# FET_mux_2layer.net
KiCad netlist of a schematic drawn in EAGLE
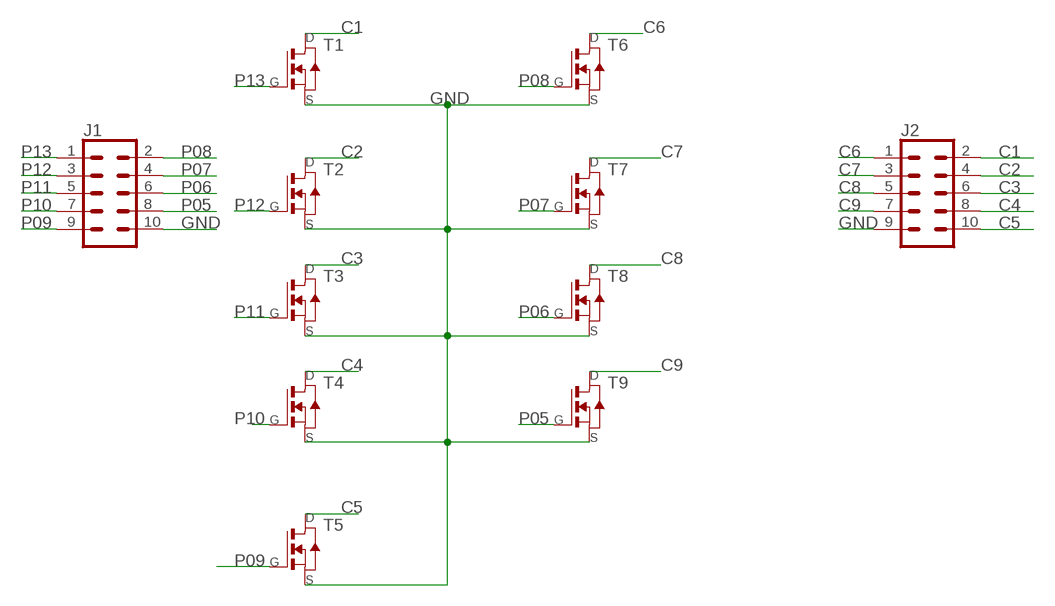
[diagram p0: schematic, sheet 1]

(export (version "E")
  (design (tool "Eeschema 10.0.6"))
  (components
    (comp (ref "J1")
      (value "CONN_05X2SHD_SMD")
      (footprint "eagle-import:2X5-SHROUDED_SMD")
      (libsource (lib "eagle-import") (part "CONN_05X2SHD_SMD"))
    )
    (comp (ref "J2")
      (value "CONN_05X2SHD_SMD")
      (footprint "eagle-import:2X5-SHROUDED_SMD")
      (libsource (lib "eagle-import") (part "CONN_05X2SHD_SMD"))
    )
    (comp (ref "T1")
      (value "NMOSFETSOT23")
      (footprint "eagle-import:SOT-23")
      (libsource (lib "eagle-import") (part "NMOSFETSOT23"))
    )
    (comp (ref "T2")
      (value "NMOSFETSOT23")
      (footprint "eagle-import:SOT-23")
      (libsource (lib "eagle-import") (part "NMOSFETSOT23"))
    )
    (comp (ref "T3")
      (value "NMOSFETSOT23")
      (footprint "eagle-import:SOT-23")
      (libsource (lib "eagle-import") (part "NMOSFETSOT23"))
    )
    (comp (ref "T4")
      (value "NMOSFETSOT23")
      (footprint "eagle-import:SOT-23")
      (libsource (lib "eagle-import") (part "NMOSFETSOT23"))
    )
    (comp (ref "T5")
      (value "NMOSFETSOT23")
      (footprint "eagle-import:SOT-23")
      (libsource (lib "eagle-import") (part "NMOSFETSOT23"))
    )
    (comp (ref "T6")
      (value "NMOSFETSOT23")
      (footprint "eagle-import:SOT-23")
      (libsource (lib "eagle-import") (part "NMOSFETSOT23"))
    )
    (comp (ref "T7")
      (value "NMOSFETSOT23")
      (footprint "eagle-import:SOT-23")
      (libsource (lib "eagle-import") (part "NMOSFETSOT23"))
    )
    (comp (ref "T8")
      (value "NMOSFETSOT23")
      (footprint "eagle-import:SOT-23")
      (libsource (lib "eagle-import") (part "NMOSFETSOT23"))
    )
    (comp (ref "T9")
      (value "NMOSFETSOT23")
      (footprint "eagle-import:SOT-23")
      (libsource (lib "eagle-import") (part "NMOSFETSOT23"))
    )
  )
  (nets
    (net (code "1") (name "/C1") (class "Default")
      (node (ref "J2") (pin "2") (pinfunction "2_2") (pintype "passive"))
      (node (ref "T1") (pin "1") (pinfunction "D_1") (pintype "passive"))
    )
    (net (code "2") (name "/C2") (class "Default")
      (node (ref "J2") (pin "4") (pinfunction "4_4") (pintype "passive"))
      (node (ref "T2") (pin "1") (pinfunction "D_1") (pintype "passive"))
    )
    (net (code "3") (name "/C3") (class "Default")
      (node (ref "J2") (pin "6") (pinfunction "6_6") (pintype "passive"))
      (node (ref "T3") (pin "1") (pinfunction "D_1") (pintype "passive"))
    )
    (net (code "4") (name "/C4") (class "Default")
      (node (ref "J2") (pin "8") (pinfunction "8_8") (pintype "passive"))
      (node (ref "T4") (pin "1") (pinfunction "D_1") (pintype "passive"))
    )
    (net (code "5") (name "/C5") (class "Default")
      (node (ref "J2") (pin "10") (pinfunction "10_10") (pintype "passive"))
      (node (ref "T5") (pin "1") (pinfunction "D_1") (pintype "passive"))
    )
    (net (code "6") (name "/C6") (class "Default")
      (node (ref "J2") (pin "1") (pinfunction "1_1") (pintype "passive"))
      (node (ref "T6") (pin "1") (pinfunction "D_1") (pintype "passive"))
    )
    (net (code "7") (name "/C7") (class "Default")
      (node (ref "J2") (pin "3") (pinfunction "3_3") (pintype "passive"))
      (node (ref "T7") (pin "1") (pinfunction "D_1") (pintype "passive"))
    )
    (net (code "8") (name "/C8") (class "Default")
      (node (ref "J2") (pin "5") (pinfunction "5_5") (pintype "passive"))
      (node (ref "T8") (pin "1") (pinfunction "D_1") (pintype "passive"))
    )
    (net (code "9") (name "/C9") (class "Default")
      (node (ref "J2") (pin "7") (pinfunction "7_7") (pintype "passive"))
      (node (ref "T9") (pin "1") (pinfunction "D_1") (pintype "passive"))
    )
    (net (code "10") (name "/GND") (class "Default")
      (node (ref "J1") (pin "10") (pinfunction "10_10") (pintype "passive"))
      (node (ref "J2") (pin "9") (pinfunction "9_9") (pintype "passive"))
      (node (ref "T1") (pin "2") (pinfunction "S_2") (pintype "passive"))
      (node (ref "T2") (pin "2") (pinfunction "S_2") (pintype "passive"))
      (node (ref "T3") (pin "2") (pinfunction "S_2") (pintype "passive"))
      (node (ref "T4") (pin "2") (pinfunction "S_2") (pintype "passive"))
      (node (ref "T5") (pin "2") (pinfunction "S_2") (pintype "passive"))
      (node (ref "T6") (pin "2") (pinfunction "S_2") (pintype "passive"))
      (node (ref "T7") (pin "2") (pinfunction "S_2") (pintype "passive"))
      (node (ref "T8") (pin "2") (pinfunction "S_2") (pintype "passive"))
      (node (ref "T9") (pin "2") (pinfunction "S_2") (pintype "passive"))
    )
    (net (code "11") (name "/P05") (class "Default")
      (node (ref "J1") (pin "8") (pinfunction "8_8") (pintype "passive"))
      (node (ref "T9") (pin "3") (pinfunction "G_3") (pintype "passive"))
    )
    (net (code "12") (name "/P06") (class "Default")
      (node (ref "J1") (pin "6") (pinfunction "6_6") (pintype "passive"))
      (node (ref "T8") (pin "3") (pinfunction "G_3") (pintype "passive"))
    )
    (net (code "13") (name "/P07") (class "Default")
      (node (ref "J1") (pin "4") (pinfunction "4_4") (pintype "passive"))
      (node (ref "T7") (pin "3") (pinfunction "G_3") (pintype "passive"))
    )
    (net (code "14") (name "/P08") (class "Default")
      (node (ref "J1") (pin "2") (pinfunction "2_2") (pintype "passive"))
      (node (ref "T6") (pin "3") (pinfunction "G_3") (pintype "passive"))
    )
    (net (code "15") (name "/P09") (class "Default")
      (node (ref "J1") (pin "9") (pinfunction "9_9") (pintype "passive"))
      (node (ref "T5") (pin "3") (pinfunction "G_3") (pintype "passive"))
    )
    (net (code "16") (name "/P10") (class "Default")
      (node (ref "J1") (pin "7") (pinfunction "7_7") (pintype "passive"))
      (node (ref "T4") (pin "3") (pinfunction "G_3") (pintype "passive"))
    )
    (net (code "17") (name "/P11") (class "Default")
      (node (ref "J1") (pin "5") (pinfunction "5_5") (pintype "passive"))
      (node (ref "T3") (pin "3") (pinfunction "G_3") (pintype "passive"))
    )
    (net (code "18") (name "/P12") (class "Default")
      (node (ref "J1") (pin "3") (pinfunction "3_3") (pintype "passive"))
      (node (ref "T2") (pin "3") (pinfunction "G_3") (pintype "passive"))
    )
    (net (code "19") (name "/P13") (class "Default")
      (node (ref "J1") (pin "1") (pinfunction "1_1") (pintype "passive"))
      (node (ref "T1") (pin "3") (pinfunction "G_3") (pintype "passive"))
    )
  )
)
